# Kasli-SOC_IDC_EXT_Connectors.net
KiCad netlist of a schematic drawn in Altium Designer
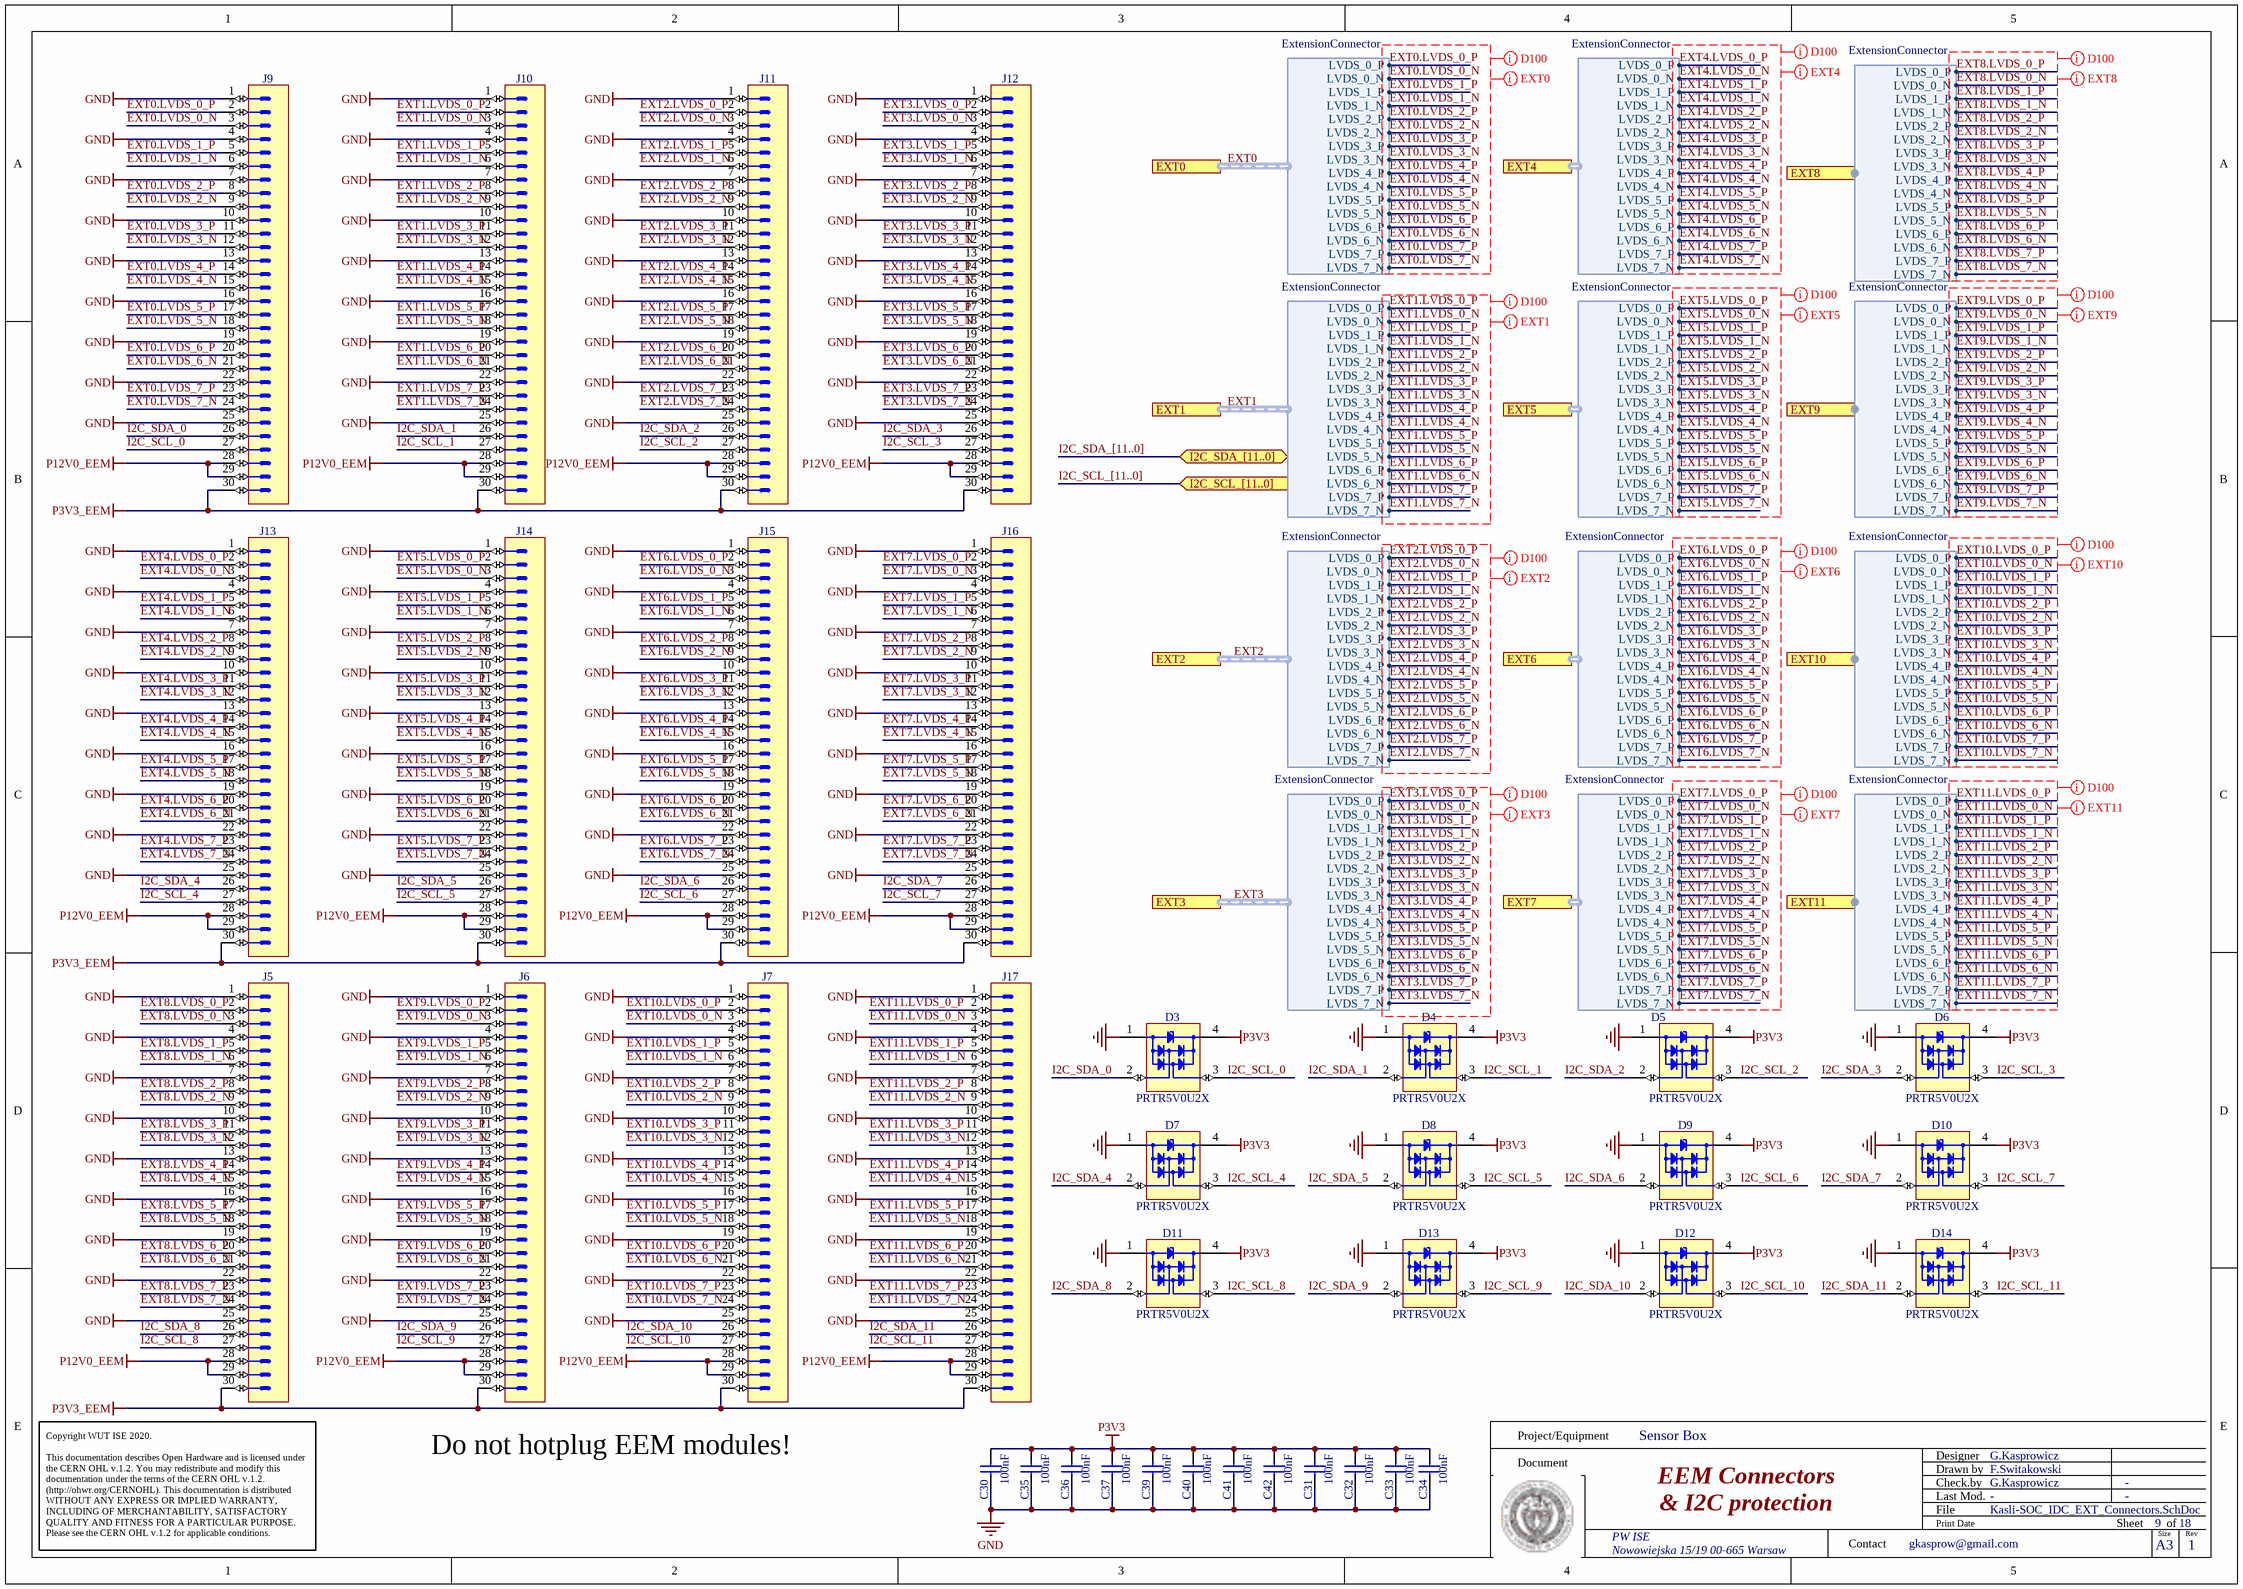
[diagram p0: Kasli-SOC_IDC_EXT_Connectors.SchDoc]

(export (version "E")
  (design (tool "Eeschema 10.0.6"))
  (components
    (comp (ref "C30")
      (value "100nF")
      (footprint "CAPC0603X33N")
      (description "Non-polarised capacitor")
      (fields
        (field (name "PART NUMBER") "CC0201_100NF_6.3V_10%_X5R")
        (field (name "VOLTAGE") "6.3V")
        (field (name "AUTHOR") "CERN DEM JLC")
      )
      (libsource (lib "Capacitors") (part "Capacitor - non polarized"))
    )
    (comp (ref "C31")
      (value "100nF")
      (footprint "CAPC0603X33N")
      (description "Non-polarised capacitor")
      (fields
        (field (name "PART NUMBER") "CC0201_100NF_6.3V_10%_X5R")
        (field (name "VOLTAGE") "6.3V")
        (field (name "AUTHOR") "CERN DEM JLC")
      )
      (libsource (lib "Capacitors") (part "Capacitor - non polarized"))
    )
    (comp (ref "C32")
      (value "100nF")
      (footprint "CAPC0603X33N")
      (description "Non-polarised capacitor")
      (fields
        (field (name "PART NUMBER") "CC0201_100NF_6.3V_10%_X5R")
        (field (name "VOLTAGE") "6.3V")
        (field (name "AUTHOR") "CERN DEM JLC")
      )
      (libsource (lib "Capacitors") (part "Capacitor - non polarized"))
    )
    (comp (ref "C33")
      (value "100nF")
      (footprint "CAPC0603X33N")
      (description "Non-polarised capacitor")
      (fields
        (field (name "PART NUMBER") "CC0201_100NF_6.3V_10%_X5R")
        (field (name "VOLTAGE") "6.3V")
        (field (name "AUTHOR") "CERN DEM JLC")
      )
      (libsource (lib "Capacitors") (part "Capacitor - non polarized"))
    )
    (comp (ref "C34")
      (value "100nF")
      (footprint "CAPC0603X33N")
      (description "Non-polarised capacitor")
      (fields
        (field (name "PART NUMBER") "CC0201_100NF_6.3V_10%_X5R")
        (field (name "VOLTAGE") "6.3V")
        (field (name "AUTHOR") "CERN DEM JLC")
      )
      (libsource (lib "Capacitors") (part "Capacitor - non polarized"))
    )
    (comp (ref "C35")
      (value "100nF")
      (footprint "CAPC0603X33N")
      (description "Non-polarised capacitor")
      (fields
        (field (name "PART NUMBER") "CC0201_100NF_6.3V_10%_X5R")
        (field (name "VOLTAGE") "6.3V")
        (field (name "AUTHOR") "CERN DEM JLC")
      )
      (libsource (lib "Capacitors") (part "Capacitor - non polarized"))
    )
    (comp (ref "C36")
      (value "100nF")
      (footprint "CAPC0603X33N")
      (description "Non-polarised capacitor")
      (fields
        (field (name "PART NUMBER") "CC0201_100NF_6.3V_10%_X5R")
        (field (name "VOLTAGE") "6.3V")
        (field (name "AUTHOR") "CERN DEM JLC")
      )
      (libsource (lib "Capacitors") (part "Capacitor - non polarized"))
    )
    (comp (ref "C37")
      (value "100nF")
      (footprint "CAPC0603X33N")
      (description "Non-polarised capacitor")
      (fields
        (field (name "PART NUMBER") "CC0201_100NF_6.3V_10%_X5R")
        (field (name "VOLTAGE") "6.3V")
        (field (name "AUTHOR") "CERN DEM JLC")
      )
      (libsource (lib "Capacitors") (part "Capacitor - non polarized"))
    )
    (comp (ref "C39")
      (value "100nF")
      (footprint "CAPC0603X33N")
      (description "Non-polarised capacitor")
      (fields
        (field (name "PART NUMBER") "CC0201_100NF_6.3V_10%_X5R")
        (field (name "VOLTAGE") "6.3V")
        (field (name "AUTHOR") "CERN DEM JLC")
      )
      (libsource (lib "Capacitors") (part "Capacitor - non polarized"))
    )
    (comp (ref "C40")
      (value "100nF")
      (footprint "CAPC0603X33N")
      (description "Non-polarised capacitor")
      (fields
        (field (name "PART NUMBER") "CC0201_100NF_6.3V_10%_X5R")
        (field (name "VOLTAGE") "6.3V")
        (field (name "AUTHOR") "CERN DEM JLC")
      )
      (libsource (lib "Capacitors") (part "Capacitor - non polarized"))
    )
    (comp (ref "C41")
      (value "100nF")
      (footprint "CAPC0603X33N")
      (description "Non-polarised capacitor")
      (fields
        (field (name "PART NUMBER") "CC0201_100NF_6.3V_10%_X5R")
        (field (name "VOLTAGE") "6.3V")
        (field (name "AUTHOR") "CERN DEM JLC")
      )
      (libsource (lib "Capacitors") (part "Capacitor - non polarized"))
    )
    (comp (ref "C42")
      (value "100nF")
      (footprint "CAPC0603X33N")
      (description "Non-polarised capacitor")
      (fields
        (field (name "PART NUMBER") "CC0201_100NF_6.3V_10%_X5R")
        (field (name "VOLTAGE") "6.3V")
        (field (name "AUTHOR") "CERN DEM JLC")
      )
      (libsource (lib "Capacitors") (part "Capacitor - non polarized"))
    )
    (comp (ref "D3")
      (value "PRTR5V0U2X")
      (footprint "SOT190P230X110-4N")
      (description "Ultra Low Capacitance Double Rail-to-Rail ESD Protection Diode")
      (fields
        (field (name "VOLTAGE") "5.5V")
        (field (name "MANUFACTURER") "NXP SEMICONDUCTORS")
        (field (name "AUTHOR") "CERN DEM JLC")
      )
      (libsource (lib "ICs And Semiconductors") (part "PRTR5V0U2X"))
    )
    (comp (ref "D4")
      (value "PRTR5V0U2X")
      (footprint "SOT190P230X110-4N")
      (description "Ultra Low Capacitance Double Rail-to-Rail ESD Protection Diode")
      (fields
        (field (name "VOLTAGE") "5.5V")
        (field (name "MANUFACTURER") "NXP SEMICONDUCTORS")
        (field (name "AUTHOR") "CERN DEM JLC")
      )
      (libsource (lib "ICs And Semiconductors") (part "PRTR5V0U2X"))
    )
    (comp (ref "D5")
      (value "PRTR5V0U2X")
      (footprint "SOT190P230X110-4N")
      (description "Ultra Low Capacitance Double Rail-to-Rail ESD Protection Diode")
      (fields
        (field (name "VOLTAGE") "5.5V")
        (field (name "MANUFACTURER") "NXP SEMICONDUCTORS")
        (field (name "AUTHOR") "CERN DEM JLC")
      )
      (libsource (lib "ICs And Semiconductors") (part "PRTR5V0U2X"))
    )
    (comp (ref "D6")
      (value "PRTR5V0U2X")
      (footprint "SOT190P230X110-4N")
      (description "Ultra Low Capacitance Double Rail-to-Rail ESD Protection Diode")
      (fields
        (field (name "VOLTAGE") "5.5V")
        (field (name "MANUFACTURER") "NXP SEMICONDUCTORS")
        (field (name "AUTHOR") "CERN DEM JLC")
      )
      (libsource (lib "ICs And Semiconductors") (part "PRTR5V0U2X"))
    )
    (comp (ref "D7")
      (value "PRTR5V0U2X")
      (footprint "SOT190P230X110-4N")
      (description "Ultra Low Capacitance Double Rail-to-Rail ESD Protection Diode")
      (fields
        (field (name "VOLTAGE") "5.5V")
        (field (name "MANUFACTURER") "NXP SEMICONDUCTORS")
        (field (name "AUTHOR") "CERN DEM JLC")
      )
      (libsource (lib "ICs And Semiconductors") (part "PRTR5V0U2X"))
    )
    (comp (ref "D8")
      (value "PRTR5V0U2X")
      (footprint "SOT190P230X110-4N")
      (description "Ultra Low Capacitance Double Rail-to-Rail ESD Protection Diode")
      (fields
        (field (name "VOLTAGE") "5.5V")
        (field (name "MANUFACTURER") "NXP SEMICONDUCTORS")
        (field (name "AUTHOR") "CERN DEM JLC")
      )
      (libsource (lib "ICs And Semiconductors") (part "PRTR5V0U2X"))
    )
    (comp (ref "D9")
      (value "PRTR5V0U2X")
      (footprint "SOT190P230X110-4N")
      (description "Ultra Low Capacitance Double Rail-to-Rail ESD Protection Diode")
      (fields
        (field (name "VOLTAGE") "5.5V")
        (field (name "MANUFACTURER") "NXP SEMICONDUCTORS")
        (field (name "AUTHOR") "CERN DEM JLC")
      )
      (libsource (lib "ICs And Semiconductors") (part "PRTR5V0U2X"))
    )
    (comp (ref "D10")
      (value "PRTR5V0U2X")
      (footprint "SOT190P230X110-4N")
      (description "Ultra Low Capacitance Double Rail-to-Rail ESD Protection Diode")
      (fields
        (field (name "VOLTAGE") "5.5V")
        (field (name "MANUFACTURER") "NXP SEMICONDUCTORS")
        (field (name "AUTHOR") "CERN DEM JLC")
      )
      (libsource (lib "ICs And Semiconductors") (part "PRTR5V0U2X"))
    )
    (comp (ref "D11")
      (value "PRTR5V0U2X")
      (footprint "SOT190P230X110-4N")
      (description "Ultra Low Capacitance Double Rail-to-Rail ESD Protection Diode")
      (fields
        (field (name "VOLTAGE") "5.5V")
        (field (name "MANUFACTURER") "NXP SEMICONDUCTORS")
        (field (name "AUTHOR") "CERN DEM JLC")
      )
      (libsource (lib "ICs And Semiconductors") (part "PRTR5V0U2X"))
    )
    (comp (ref "D12")
      (value "PRTR5V0U2X")
      (footprint "SOT190P230X110-4N")
      (description "Ultra Low Capacitance Double Rail-to-Rail ESD Protection Diode")
      (fields
        (field (name "VOLTAGE") "5.5V")
        (field (name "MANUFACTURER") "NXP SEMICONDUCTORS")
        (field (name "AUTHOR") "CERN DEM JLC")
      )
      (libsource (lib "ICs And Semiconductors") (part "PRTR5V0U2X"))
    )
    (comp (ref "D13")
      (value "PRTR5V0U2X")
      (footprint "SOT190P230X110-4N")
      (description "Ultra Low Capacitance Double Rail-to-Rail ESD Protection Diode")
      (fields
        (field (name "VOLTAGE") "5.5V")
        (field (name "MANUFACTURER") "NXP SEMICONDUCTORS")
        (field (name "AUTHOR") "CERN DEM JLC")
      )
      (libsource (lib "ICs And Semiconductors") (part "PRTR5V0U2X"))
    )
    (comp (ref "D14")
      (value "PRTR5V0U2X")
      (footprint "SOT190P230X110-4N")
      (description "Ultra Low Capacitance Double Rail-to-Rail ESD Protection Diode")
      (fields
        (field (name "VOLTAGE") "5.5V")
        (field (name "MANUFACTURER") "NXP SEMICONDUCTORS")
        (field (name "AUTHOR") "CERN DEM JLC")
      )
      (libsource (lib "ICs And Semiconductors") (part "PRTR5V0U2X"))
    )
    (comp (ref "J5")
      (value "~")
      (footprint "3M_N2530-6002RB")
      (description "Connector 30 Male")
      (fields
        (field (name "PART NUMBER") "3M_N2530-6002RB")
        (field (name "MANUFACTURER") "3M")
        (field (name "AUTHOR") "CERN DEM JLC")
      )
      (libsource (lib "Connectors") (part "Connector 30 Male"))
    )
    (comp (ref "J6")
      (value "~")
      (footprint "3M_N2530-6002RB")
      (description "Connector 30 Male")
      (fields
        (field (name "PART NUMBER") "3M_N2530-6002RB")
        (field (name "MANUFACTURER") "3M")
        (field (name "AUTHOR") "CERN DEM JLC")
      )
      (libsource (lib "Connectors") (part "Connector 30 Male"))
    )
    (comp (ref "J7")
      (value "~")
      (footprint "3M_N2530-6002RB")
      (description "Connector 30 Male")
      (fields
        (field (name "PART NUMBER") "3M_N2530-6002RB")
        (field (name "MANUFACTURER") "3M")
        (field (name "AUTHOR") "CERN DEM JLC")
      )
      (libsource (lib "Connectors") (part "Connector 30 Male"))
    )
    (comp (ref "J9")
      (value "~")
      (footprint "3M_N2530-6002RB")
      (description "Connector 30 Male")
      (fields
        (field (name "PART NUMBER") "3M_N2530-6002RB")
        (field (name "MANUFACTURER") "3M")
        (field (name "AUTHOR") "CERN DEM JLC")
      )
      (libsource (lib "Connectors") (part "Connector 30 Male"))
    )
    (comp (ref "J10")
      (value "~")
      (footprint "3M_N2530-6002RB")
      (description "Connector 30 Male")
      (fields
        (field (name "PART NUMBER") "3M_N2530-6002RB")
        (field (name "MANUFACTURER") "3M")
        (field (name "AUTHOR") "CERN DEM JLC")
      )
      (libsource (lib "Connectors") (part "Connector 30 Male"))
    )
    (comp (ref "J11")
      (value "~")
      (footprint "3M_N2530-6002RB")
      (description "Connector 30 Male")
      (fields
        (field (name "PART NUMBER") "3M_N2530-6002RB")
        (field (name "MANUFACTURER") "3M")
        (field (name "AUTHOR") "CERN DEM JLC")
      )
      (libsource (lib "Connectors") (part "Connector 30 Male"))
    )
    (comp (ref "J12")
      (value "~")
      (footprint "3M_N2530-6002RB")
      (description "Connector 30 Male")
      (fields
        (field (name "PART NUMBER") "3M_N2530-6002RB")
        (field (name "MANUFACTURER") "3M")
        (field (name "AUTHOR") "CERN DEM JLC")
      )
      (libsource (lib "Connectors") (part "Connector 30 Male"))
    )
    (comp (ref "J13")
      (value "~")
      (footprint "3M_N2530-6002RB")
      (description "Connector 30 Male")
      (fields
        (field (name "PART NUMBER") "3M_N2530-6002RB")
        (field (name "MANUFACTURER") "3M")
        (field (name "AUTHOR") "CERN DEM JLC")
      )
      (libsource (lib "Connectors") (part "Connector 30 Male"))
    )
    (comp (ref "J14")
      (value "~")
      (footprint "3M_N2530-6002RB")
      (description "Connector 30 Male")
      (fields
        (field (name "PART NUMBER") "3M_N2530-6002RB")
        (field (name "MANUFACTURER") "3M")
        (field (name "AUTHOR") "CERN DEM JLC")
      )
      (libsource (lib "Connectors") (part "Connector 30 Male"))
    )
    (comp (ref "J15")
      (value "~")
      (footprint "3M_N2530-6002RB")
      (description "Connector 30 Male")
      (fields
        (field (name "PART NUMBER") "3M_N2530-6002RB")
        (field (name "MANUFACTURER") "3M")
        (field (name "AUTHOR") "CERN DEM JLC")
      )
      (libsource (lib "Connectors") (part "Connector 30 Male"))
    )
    (comp (ref "J16")
      (value "~")
      (footprint "3M_N2530-6002RB")
      (description "Connector 30 Male")
      (fields
        (field (name "PART NUMBER") "3M_N2530-6002RB")
        (field (name "MANUFACTURER") "3M")
        (field (name "AUTHOR") "CERN DEM JLC")
      )
      (libsource (lib "Connectors") (part "Connector 30 Male"))
    )
    (comp (ref "J17")
      (value "~")
      (footprint "3M_N2530-6002RB")
      (description "Connector 30 Male")
      (fields
        (field (name "PART NUMBER") "3M_N2530-6002RB")
        (field (name "MANUFACTURER") "3M")
        (field (name "AUTHOR") "CERN DEM JLC")
      )
      (libsource (lib "Connectors") (part "Connector 30 Male"))
    )
  )
  (nets
    (net (code "6") (name "/EXT0.LVDS_0_N") (class "Default")
      (node (ref "J9") (pin "3") (pinfunction "3_3") (pintype "bidirectional"))
    )
    (net (code "7") (name "/EXT0.LVDS_0_P") (class "Default")
      (node (ref "J9") (pin "2") (pinfunction "2_2") (pintype "bidirectional"))
    )
    (net (code "8") (name "/EXT0.LVDS_1_N") (class "Default")
      (node (ref "J9") (pin "6") (pinfunction "6_6") (pintype "bidirectional"))
    )
    (net (code "9") (name "/EXT0.LVDS_1_P") (class "Default")
      (node (ref "J9") (pin "5") (pinfunction "5_5") (pintype "bidirectional"))
    )
    (net (code "10") (name "/EXT0.LVDS_2_N") (class "Default")
      (node (ref "J9") (pin "9") (pinfunction "9_9") (pintype "bidirectional"))
    )
    (net (code "11") (name "/EXT0.LVDS_2_P") (class "Default")
      (node (ref "J9") (pin "8") (pinfunction "8_8") (pintype "bidirectional"))
    )
    (net (code "12") (name "/EXT0.LVDS_3_N") (class "Default")
      (node (ref "J9") (pin "12") (pinfunction "12_12") (pintype "bidirectional"))
    )
    (net (code "13") (name "/EXT0.LVDS_3_P") (class "Default")
      (node (ref "J9") (pin "11") (pinfunction "11_11") (pintype "bidirectional"))
    )
    (net (code "14") (name "/EXT0.LVDS_4_N") (class "Default")
      (node (ref "J9") (pin "15") (pinfunction "15_15") (pintype "bidirectional"))
    )
    (net (code "15") (name "/EXT0.LVDS_4_P") (class "Default")
      (node (ref "J9") (pin "14") (pinfunction "14_14") (pintype "bidirectional"))
    )
    (net (code "16") (name "/EXT0.LVDS_5_N") (class "Default")
      (node (ref "J9") (pin "18") (pinfunction "18_18") (pintype "bidirectional"))
    )
    (net (code "17") (name "/EXT0.LVDS_5_P") (class "Default")
      (node (ref "J9") (pin "17") (pinfunction "17_17") (pintype "bidirectional"))
    )
    (net (code "18") (name "/EXT0.LVDS_6_N") (class "Default")
      (node (ref "J9") (pin "21") (pinfunction "21_21") (pintype "bidirectional"))
    )
    (net (code "19") (name "/EXT0.LVDS_6_P") (class "Default")
      (node (ref "J9") (pin "20") (pinfunction "20_20") (pintype "bidirectional"))
    )
    (net (code "20") (name "/EXT0.LVDS_7_N") (class "Default")
      (node (ref "J9") (pin "24") (pinfunction "24_24") (pintype "bidirectional"))
    )
    (net (code "21") (name "/EXT0.LVDS_7_P") (class "Default")
      (node (ref "J9") (pin "23") (pinfunction "23_23") (pintype "bidirectional"))
    )
    (net (code "23") (name "/EXT1.LVDS_0_N") (class "Default")
      (node (ref "J10") (pin "3") (pinfunction "3_3") (pintype "bidirectional"))
    )
    (net (code "24") (name "/EXT1.LVDS_0_P") (class "Default")
      (node (ref "J10") (pin "2") (pinfunction "2_2") (pintype "bidirectional"))
    )
    (net (code "25") (name "/EXT1.LVDS_1_N") (class "Default")
      (node (ref "J10") (pin "6") (pinfunction "6_6") (pintype "bidirectional"))
    )
    (net (code "26") (name "/EXT1.LVDS_1_P") (class "Default")
      (node (ref "J10") (pin "5") (pinfunction "5_5") (pintype "bidirectional"))
    )
    (net (code "27") (name "/EXT1.LVDS_2_N") (class "Default")
      (node (ref "J10") (pin "9") (pinfunction "9_9") (pintype "bidirectional"))
    )
    (net (code "28") (name "/EXT1.LVDS_2_P") (class "Default")
      (node (ref "J10") (pin "8") (pinfunction "8_8") (pintype "bidirectional"))
    )
    (net (code "29") (name "/EXT1.LVDS_3_N") (class "Default")
      (node (ref "J10") (pin "12") (pinfunction "12_12") (pintype "bidirectional"))
    )
    (net (code "30") (name "/EXT1.LVDS_3_P") (class "Default")
      (node (ref "J10") (pin "11") (pinfunction "11_11") (pintype "bidirectional"))
    )
    (net (code "31") (name "/EXT1.LVDS_4_N") (class "Default")
      (node (ref "J10") (pin "15") (pinfunction "15_15") (pintype "bidirectional"))
    )
    (net (code "32") (name "/EXT1.LVDS_4_P") (class "Default")
      (node (ref "J10") (pin "14") (pinfunction "14_14") (pintype "bidirectional"))
    )
    (net (code "33") (name "/EXT1.LVDS_5_N") (class "Default")
      (node (ref "J10") (pin "18") (pinfunction "18_18") (pintype "bidirectional"))
    )
    (net (code "34") (name "/EXT1.LVDS_5_P") (class "Default")
      (node (ref "J10") (pin "17") (pinfunction "17_17") (pintype "bidirectional"))
    )
    (net (code "35") (name "/EXT1.LVDS_6_N") (class "Default")
      (node (ref "J10") (pin "21") (pinfunction "21_21") (pintype "bidirectional"))
    )
    (net (code "36") (name "/EXT1.LVDS_6_P") (class "Default")
      (node (ref "J10") (pin "20") (pinfunction "20_20") (pintype "bidirectional"))
    )
    (net (code "37") (name "/EXT1.LVDS_7_N") (class "Default")
      (node (ref "J10") (pin "24") (pinfunction "24_24") (pintype "bidirectional"))
    )
    (net (code "38") (name "/EXT1.LVDS_7_P") (class "Default")
      (node (ref "J10") (pin "23") (pinfunction "23_23") (pintype "bidirectional"))
    )
    (net (code "40") (name "/EXT2.LVDS_0_N") (class "Default")
      (node (ref "J11") (pin "3") (pinfunction "3_3") (pintype "bidirectional"))
    )
    (net (code "41") (name "/EXT2.LVDS_0_P") (class "Default")
      (node (ref "J11") (pin "2") (pinfunction "2_2") (pintype "bidirectional"))
    )
    (net (code "42") (name "/EXT2.LVDS_1_N") (class "Default")
      (node (ref "J11") (pin "6") (pinfunction "6_6") (pintype "bidirectional"))
    )
    (net (code "43") (name "/EXT2.LVDS_1_P") (class "Default")
      (node (ref "J11") (pin "5") (pinfunction "5_5") (pintype "bidirectional"))
    )
    (net (code "44") (name "/EXT2.LVDS_2_N") (class "Default")
      (node (ref "J11") (pin "9") (pinfunction "9_9") (pintype "bidirectional"))
    )
    (net (code "45") (name "/EXT2.LVDS_2_P") (class "Default")
      (node (ref "J11") (pin "8") (pinfunction "8_8") (pintype "bidirectional"))
    )
    (net (code "46") (name "/EXT2.LVDS_3_N") (class "Default")
      (node (ref "J11") (pin "12") (pinfunction "12_12") (pintype "bidirectional"))
    )
    (net (code "47") (name "/EXT2.LVDS_3_P") (class "Default")
      (node (ref "J11") (pin "11") (pinfunction "11_11") (pintype "bidirectional"))
    )
    (net (code "48") (name "/EXT2.LVDS_4_N") (class "Default")
      (node (ref "J11") (pin "15") (pinfunction "15_15") (pintype "bidirectional"))
    )
    (net (code "49") (name "/EXT2.LVDS_4_P") (class "Default")
      (node (ref "J11") (pin "14") (pinfunction "14_14") (pintype "bidirectional"))
    )
    (net (code "50") (name "/EXT2.LVDS_5_N") (class "Default")
      (node (ref "J11") (pin "18") (pinfunction "18_18") (pintype "bidirectional"))
    )
    (net (code "51") (name "/EXT2.LVDS_5_P") (class "Default")
      (node (ref "J11") (pin "17") (pinfunction "17_17") (pintype "bidirectional"))
    )
    (net (code "52") (name "/EXT2.LVDS_6_N") (class "Default")
      (node (ref "J11") (pin "21") (pinfunction "21_21") (pintype "bidirectional"))
    )
    (net (code "53") (name "/EXT2.LVDS_6_P") (class "Default")
      (node (ref "J11") (pin "20") (pinfunction "20_20") (pintype "bidirectional"))
    )
    (net (code "54") (name "/EXT2.LVDS_7_N") (class "Default")
      (node (ref "J11") (pin "24") (pinfunction "24_24") (pintype "bidirectional"))
    )
    (net (code "55") (name "/EXT2.LVDS_7_P") (class "Default")
      (node (ref "J11") (pin "23") (pinfunction "23_23") (pintype "bidirectional"))
    )
    (net (code "57") (name "/EXT3.LVDS_0_N") (class "Default")
      (node (ref "J12") (pin "3") (pinfunction "3_3") (pintype "bidirectional"))
    )
    (net (code "58") (name "/EXT3.LVDS_0_P") (class "Default")
      (node (ref "J12") (pin "2") (pinfunction "2_2") (pintype "bidirectional"))
    )
    (net (code "59") (name "/EXT3.LVDS_1_N") (class "Default")
      (node (ref "J12") (pin "6") (pinfunction "6_6") (pintype "bidirectional"))
    )
    (net (code "60") (name "/EXT3.LVDS_1_P") (class "Default")
      (node (ref "J12") (pin "5") (pinfunction "5_5") (pintype "bidirectional"))
    )
    (net (code "61") (name "/EXT3.LVDS_2_N") (class "Default")
      (node (ref "J12") (pin "9") (pinfunction "9_9") (pintype "bidirectional"))
    )
    (net (code "62") (name "/EXT3.LVDS_2_P") (class "Default")
      (node (ref "J12") (pin "8") (pinfunction "8_8") (pintype "bidirectional"))
    )
    (net (code "63") (name "/EXT3.LVDS_3_N") (class "Default")
      (node (ref "J12") (pin "12") (pinfunction "12_12") (pintype "bidirectional"))
    )
    (net (code "64") (name "/EXT3.LVDS_3_P") (class "Default")
      (node (ref "J12") (pin "11") (pinfunction "11_11") (pintype "bidirectional"))
    )
    (net (code "65") (name "/EXT3.LVDS_4_N") (class "Default")
      (node (ref "J12") (pin "15") (pinfunction "15_15") (pintype "bidirectional"))
    )
    (net (code "66") (name "/EXT3.LVDS_4_P") (class "Default")
      (node (ref "J12") (pin "14") (pinfunction "14_14") (pintype "bidirectional"))
    )
    (net (code "67") (name "/EXT3.LVDS_5_N") (class "Default")
      (node (ref "J12") (pin "18") (pinfunction "18_18") (pintype "bidirectional"))
    )
    (net (code "68") (name "/EXT3.LVDS_5_P") (class "Default")
      (node (ref "J12") (pin "17") (pinfunction "17_17") (pintype "bidirectional"))
    )
    (net (code "69") (name "/EXT3.LVDS_6_N") (class "Default")
      (node (ref "J12") (pin "21") (pinfunction "21_21") (pintype "bidirectional"))
    )
    (net (code "70") (name "/EXT3.LVDS_6_P") (class "Default")
      (node (ref "J12") (pin "20") (pinfunction "20_20") (pintype "bidirectional"))
    )
    (net (code "71") (name "/EXT3.LVDS_7_N") (class "Default")
      (node (ref "J12") (pin "24") (pinfunction "24_24") (pintype "bidirectional"))
    )
    (net (code "72") (name "/EXT3.LVDS_7_P") (class "Default")
      (node (ref "J12") (pin "23") (pinfunction "23_23") (pintype "bidirectional"))
    )
    (net (code "74") (name "/EXT4.LVDS_0_N") (class "Default")
      (node (ref "J13") (pin "3") (pinfunction "3_3") (pintype "bidirectional"))
    )
    (net (code "75") (name "/EXT4.LVDS_0_P") (class "Default")
      (node (ref "J13") (pin "2") (pinfunction "2_2") (pintype "bidirectional"))
    )
    (net (code "76") (name "/EXT4.LVDS_1_N") (class "Default")
      (node (ref "J13") (pin "6") (pinfunction "6_6") (pintype "bidirectional"))
    )
    (net (code "77") (name "/EXT4.LVDS_1_P") (class "Default")
      (node (ref "J13") (pin "5") (pinfunction "5_5") (pintype "bidirectional"))
    )
    (net (code "78") (name "/EXT4.LVDS_2_N") (class "Default")
      (node (ref "J13") (pin "9") (pinfunction "9_9") (pintype "bidirectional"))
    )
    (net (code "79") (name "/EXT4.LVDS_2_P") (class "Default")
      (node (ref "J13") (pin "8") (pinfunction "8_8") (pintype "bidirectional"))
    )
    (net (code "80") (name "/EXT4.LVDS_3_N") (class "Default")
      (node (ref "J13") (pin "12") (pinfunction "12_12") (pintype "bidirectional"))
    )
    (net (code "81") (name "/EXT4.LVDS_3_P") (class "Default")
      (node (ref "J13") (pin "11") (pinfunction "11_11") (pintype "bidirectional"))
    )
    (net (code "82") (name "/EXT4.LVDS_4_N") (class "Default")
      (node (ref "J13") (pin "15") (pinfunction "15_15") (pintype "bidirectional"))
    )
    (net (code "83") (name "/EXT4.LVDS_4_P") (class "Default")
      (node (ref "J13") (pin "14") (pinfunction "14_14") (pintype "bidirectional"))
    )
    (net (code "84") (name "/EXT4.LVDS_5_N") (class "Default")
      (node (ref "J13") (pin "18") (pinfunction "18_18") (pintype "bidirectional"))
    )
    (net (code "85") (name "/EXT4.LVDS_5_P") (class "Default")
      (node (ref "J13") (pin "17") (pinfunction "17_17") (pintype "bidirectional"))
    )
    (net (code "86") (name "/EXT4.LVDS_6_N") (class "Default")
      (node (ref "J13") (pin "21") (pinfunction "21_21") (pintype "bidirectional"))
    )
    (net (code "87") (name "/EXT4.LVDS_6_P") (class "Default")
      (node (ref "J13") (pin "20") (pinfunction "20_20") (pintype "bidirectional"))
    )
    (net (code "88") (name "/EXT4.LVDS_7_N") (class "Default")
      (node (ref "J13") (pin "24") (pinfunction "24_24") (pintype "bidirectional"))
    )
    (net (code "89") (name "/EXT4.LVDS_7_P") (class "Default")
      (node (ref "J13") (pin "23") (pinfunction "23_23") (pintype "bidirectional"))
    )
    (net (code "90") (name "/EXT5.LVDS_0_N") (class "Default")
      (node (ref "J14") (pin "3") (pinfunction "3_3") (pintype "bidirectional"))
    )
    (net (code "91") (name "/EXT5.LVDS_0_P") (class "Default")
      (node (ref "J14") (pin "2") (pinfunction "2_2") (pintype "bidirectional"))
    )
    (net (code "92") (name "/EXT5.LVDS_1_N") (class "Default")
      (node (ref "J14") (pin "6") (pinfunction "6_6") (pintype "bidirectional"))
    )
    (net (code "93") (name "/EXT5.LVDS_1_P") (class "Default")
      (node (ref "J14") (pin "5") (pinfunction "5_5") (pintype "bidirectional"))
    )
    (net (code "94") (name "/EXT5.LVDS_2_N") (class "Default")
      (node (ref "J14") (pin "9") (pinfunction "9_9") (pintype "bidirectional"))
    )
    (net (code "95") (name "/EXT5.LVDS_2_P") (class "Default")
      (node (ref "J14") (pin "8") (pinfunction "8_8") (pintype "bidirectional"))
    )
    (net (code "96") (name "/EXT5.LVDS_3_N") (class "Default")
      (node (ref "J14") (pin "12") (pinfunction "12_12") (pintype "bidirectional"))
    )
    (net (code "97") (name "/EXT5.LVDS_3_P") (class "Default")
      (node (ref "J14") (pin "11") (pinfunction "11_11") (pintype "bidirectional"))
    )
    (net (code "98") (name "/EXT5.LVDS_4_N") (class "Default")
      (node (ref "J14") (pin "15") (pinfunction "15_15") (pintype "bidirectional"))
    )
    (net (code "99") (name "/EXT5.LVDS_4_P") (class "Default")
      (node (ref "J14") (pin "14") (pinfunction "14_14") (pintype "bidirectional"))
    )
    (net (code "100") (name "/EXT5.LVDS_5_N") (class "Default")
      (node (ref "J14") (pin "18") (pinfunction "18_18") (pintype "bidirectional"))
    )
    (net (code "101") (name "/EXT5.LVDS_5_P") (class "Default")
      (node (ref "J14") (pin "17") (pinfunction "17_17") (pintype "bidirectional"))
    )
    (net (code "102") (name "/EXT5.LVDS_6_N") (class "Default")
      (node (ref "J14") (pin "21") (pinfunction "21_21") (pintype "bidirectional"))
    )
    (net (code "103") (name "/EXT5.LVDS_6_P") (class "Default")
      (node (ref "J14") (pin "20") (pinfunction "20_20") (pintype "bidirectional"))
    )
    (net (code "104") (name "/EXT5.LVDS_7_N") (class "Default")
      (node (ref "J14") (pin "24") (pinfunction "24_24") (pintype "bidirectional"))
    )
    (net (code "105") (name "/EXT5.LVDS_7_P") (class "Default")
      (node (ref "J14") (pin "23") (pinfunction "23_23") (pintype "bidirectional"))
    )
    (net (code "106") (name "/EXT6.LVDS_0_N") (class "Default")
      (node (ref "J15") (pin "3") (pinfunction "3_3") (pintype "bidirectional"))
    )
    (net (code "107") (name "/EXT6.LVDS_0_P") (class "Default")
      (node (ref "J15") (pin "2") (pinfunction "2_2") (pintype "bidirectional"))
    )
    (net (code "108") (name "/EXT6.LVDS_1_N") (class "Default")
      (node (ref "J15") (pin "6") (pinfunction "6_6") (pintype "bidirectional"))
    )
    (net (code "109") (name "/EXT6.LVDS_1_P") (class "Default")
      (node (ref "J15") (pin "5") (pinfunction "5_5") (pintype "bidirectional"))
    )
    (net (code "110") (name "/EXT6.LVDS_2_N") (class "Default")
      (node (ref "J15") (pin "9") (pinfunction "9_9") (pintype "bidirectional"))
    )
    (net (code "111") (name "/EXT6.LVDS_2_P") (class "Default")
      (node (ref "J15") (pin "8") (pinfunction "8_8") (pintype "bidirectional"))
    )
    (net (code "112") (name "/EXT6.LVDS_3_N") (class "Default")
      (node (ref "J15") (pin "12") (pinfunction "12_12") (pintype "bidirectional"))
    )
    (net (code "113") (name "/EXT6.LVDS_3_P") (class "Default")
      (node (ref "J15") (pin "11") (pinfunction "11_11") (pintype "bidirectional"))
    )
    (net (code "114") (name "/EXT6.LVDS_4_N") (class "Default")
      (node (ref "J15") (pin "15") (pinfunction "15_15") (pintype "bidirectional"))
    )
    (net (code "115") (name "/EXT6.LVDS_4_P") (class "Default")
      (node (ref "J15") (pin "14") (pinfunction "14_14") (pintype "bidirectional"))
    )
    (net (code "116") (name "/EXT6.LVDS_5_N") (class "Default")
      (node (ref "J15") (pin "18") (pinfunction "18_18") (pintype "bidirectional"))
    )
    (net (code "117") (name "/EXT6.LVDS_5_P") (class "Default")
      (node (ref "J15") (pin "17") (pinfunction "17_17") (pintype "bidirectional"))
    )
    (net (code "118") (name "/EXT6.LVDS_6_N") (class "Default")
      (node (ref "J15") (pin "21") (pinfunction "21_21") (pintype "bidirectional"))
    )
    (net (code "119") (name "/EXT6.LVDS_6_P") (class "Default")
      (node (ref "J15") (pin "20") (pinfunction "20_20") (pintype "bidirectional"))
    )
    (net (code "120") (name "/EXT6.LVDS_7_N") (class "Default")
      (node (ref "J15") (pin "24") (pinfunction "24_24") (pintype "bidirectional"))
    )
    (net (code "121") (name "/EXT6.LVDS_7_P") (class "Default")
      (node (ref "J15") (pin "23") (pinfunction "23_23") (pintype "bidirectional"))
    )
    (net (code "122") (name "/EXT7.LVDS_0_N") (class "Default")
      (node (ref "J16") (pin "3") (pinfunction "3_3") (pintype "bidirectional"))
    )
    (net (code "123") (name "/EXT7.LVDS_0_P") (class "Default")
      (node (ref "J16") (pin "2") (pinfunction "2_2") (pintype "bidirectional"))
    )
    (net (code "124") (name "/EXT7.LVDS_1_N") (class "Default")
      (node (ref "J16") (pin "6") (pinfunction "6_6") (pintype "bidirectional"))
    )
    (net (code "125") (name "/EXT7.LVDS_1_P") (class "Default")
      (node (ref "J16") (pin "5") (pinfunction "5_5") (pintype "bidirectional"))
    )
    (net (code "126") (name "/EXT7.LVDS_2_N") (class "Default")
      (node (ref "J16") (pin "9") (pinfunction "9_9") (pintype "bidirectional"))
    )
    (net (code "127") (name "/EXT7.LVDS_2_P") (class "Default")
      (node (ref "J16") (pin "8") (pinfunction "8_8") (pintype "bidirectional"))
    )
    (net (code "128") (name "/EXT7.LVDS_3_N") (class "Default")
      (node (ref "J16") (pin "12") (pinfunction "12_12") (pintype "bidirectional"))
    )
    (net (code "129") (name "/EXT7.LVDS_3_P") (class "Default")
      (node (ref "J16") (pin "11") (pinfunction "11_11") (pintype "bidirectional"))
    )
    (net (code "130") (name "/EXT7.LVDS_4_N") (class "Default")
      (node (ref "J16") (pin "15") (pinfunction "15_15") (pintype "bidirectional"))
    )
    (net (code "131") (name "/EXT7.LVDS_4_P") (class "Default")
      (node (ref "J16") (pin "14") (pinfunction "14_14") (pintype "bidirectional"))
    )
    (net (code "132") (name "/EXT7.LVDS_5_N") (class "Default")
      (node (ref "J16") (pin "18") (pinfunction "18_18") (pintype "bidirectional"))
    )
    (net (code "133") (name "/EXT7.LVDS_5_P") (class "Default")
      (node (ref "J16") (pin "17") (pinfunction "17_17") (pintype "bidirectional"))
    )
    (net (code "134") (name "/EXT7.LVDS_6_N") (class "Default")
      (node (ref "J16") (pin "21") (pinfunction "21_21") (pintype "bidirectional"))
    )
    (net (code "135") (name "/EXT7.LVDS_6_P") (class "Default")
      (node (ref "J16") (pin "20") (pinfunction "20_20") (pintype "bidirectional"))
    )
    (net (code "136") (name "/EXT7.LVDS_7_N") (class "Default")
      (node (ref "J16") (pin "24") (pinfunction "24_24") (pintype "bidirectional"))
    )
    (net (code "137") (name "/EXT7.LVDS_7_P") (class "Default")
      (node (ref "J16") (pin "23") (pinfunction "23_23") (pintype "bidirectional"))
    )
    (net (code "138") (name "/EXT8.LVDS_0_N") (class "Default")
      (node (ref "J5") (pin "3") (pinfunction "3_3") (pintype "bidirectional"))
    )
    (net (code "139") (name "/EXT8.LVDS_0_P") (class "Default")
      (node (ref "J5") (pin "2") (pinfunction "2_2") (pintype "bidirectional"))
    )
    (net (code "140") (name "/EXT8.LVDS_1_N") (class "Default")
      (node (ref "J5") (pin "6") (pinfunction "6_6") (pintype "bidirectional"))
    )
    (net (code "141") (name "/EXT8.LVDS_1_P") (class "Default")
      (node (ref "J5") (pin "5") (pinfunction "5_5") (pintype "bidirectional"))
    )
    (net (code "142") (name "/EXT8.LVDS_2_N") (class "Default")
      (node (ref "J5") (pin "9") (pinfunction "9_9") (pintype "bidirectional"))
    )
    (net (code "143") (name "/EXT8.LVDS_2_P") (class "Default")
      (node (ref "J5") (pin "8") (pinfunction "8_8") (pintype "bidirectional"))
    )
    (net (code "144") (name "/EXT8.LVDS_3_N") (class "Default")
      (node (ref "J5") (pin "12") (pinfunction "12_12") (pintype "bidirectional"))
    )
    (net (code "145") (name "/EXT8.LVDS_3_P") (class "Default")
      (node (ref "J5") (pin "11") (pinfunction "11_11") (pintype "bidirectional"))
    )
    (net (code "146") (name "/EXT8.LVDS_4_N") (class "Default")
      (node (ref "J5") (pin "15") (pinfunction "15_15") (pintype "bidirectional"))
    )
    (net (code "147") (name "/EXT8.LVDS_4_P") (class "Default")
      (node (ref "J5") (pin "14") (pinfunction "14_14") (pintype "bidirectional"))
    )
    (net (code "148") (name "/EXT8.LVDS_5_N") (class "Default")
      (node (ref "J5") (pin "18") (pinfunction "18_18") (pintype "bidirectional"))
    )
    (net (code "149") (name "/EXT8.LVDS_5_P") (class "Default")
      (node (ref "J5") (pin "17") (pinfunction "17_17") (pintype "bidirectional"))
    )
    (net (code "150") (name "/EXT8.LVDS_6_N") (class "Default")
      (node (ref "J5") (pin "21") (pinfunction "21_21") (pintype "bidirectional"))
    )
    (net (code "151") (name "/EXT8.LVDS_6_P") (class "Default")
      (node (ref "J5") (pin "20") (pinfunction "20_20") (pintype "bidirectional"))
    )
    (net (code "152") (name "/EXT8.LVDS_7_N") (class "Default")
      (node (ref "J5") (pin "24") (pinfunction "24_24") (pintype "bidirectional"))
    )
    (net (code "153") (name "/EXT8.LVDS_7_P") (class "Default")
      (node (ref "J5") (pin "23") (pinfunction "23_23") (pintype "bidirectional"))
    )
    (net (code "154") (name "/EXT9.LVDS_0_N") (class "Default")
      (node (ref "J6") (pin "3") (pinfunction "3_3") (pintype "bidirectional"))
    )
    (net (code "155") (name "/EXT9.LVDS_0_P") (class "Default")
      (node (ref "J6") (pin "2") (pinfunction "2_2") (pintype "bidirectional"))
    )
    (net (code "156") (name "/EXT9.LVDS_1_N") (class "Default")
      (node (ref "J6") (pin "6") (pinfunction "6_6") (pintype "bidirectional"))
    )
    (net (code "157") (name "/EXT9.LVDS_1_P") (class "Default")
      (node (ref "J6") (pin "5") (pinfunction "5_5") (pintype "bidirectional"))
    )
    (net (code "158") (name "/EXT9.LVDS_2_N") (class "Default")
      (node (ref "J6") (pin "9") (pinfunction "9_9") (pintype "bidirectional"))
    )
    (net (code "159") (name "/EXT9.LVDS_2_P") (class "Default")
      (node (ref "J6") (pin "8") (pinfunction "8_8") (pintype "bidirectional"))
    )
    (net (code "160") (name "/EXT9.LVDS_3_N") (class "Default")
      (node (ref "J6") (pin "12") (pinfunction "12_12") (pintype "bidirectional"))
    )
    (net (code "161") (name "/EXT9.LVDS_3_P") (class "Default")
      (node (ref "J6") (pin "11") (pinfunction "11_11") (pintype "bidirectional"))
    )
    (net (code "162") (name "/EXT9.LVDS_4_N") (class "Default")
      (node (ref "J6") (pin "15") (pinfunction "15_15") (pintype "bidirectional"))
    )
    (net (code "163") (name "/EXT9.LVDS_4_P") (class "Default")
      (node (ref "J6") (pin "14") (pinfunction "14_14") (pintype "bidirectional"))
    )
    (net (code "164") (name "/EXT9.LVDS_5_N") (class "Default")
      (node (ref "J6") (pin "18") (pinfunction "18_18") (pintype "bidirectional"))
    )
    (net (code "165") (name "/EXT9.LVDS_5_P") (class "Default")
      (node (ref "J6") (pin "17") (pinfunction "17_17") (pintype "bidirectional"))
    )
    (net (code "166") (name "/EXT9.LVDS_6_N") (class "Default")
      (node (ref "J6") (pin "21") (pinfunction "21_21") (pintype "bidirectional"))
    )
    (net (code "167") (name "/EXT9.LVDS_6_P") (class "Default")
      (node (ref "J6") (pin "20") (pinfunction "20_20") (pintype "bidirectional"))
    )
    (net (code "168") (name "/EXT9.LVDS_7_N") (class "Default")
      (node (ref "J6") (pin "24") (pinfunction "24_24") (pintype "bidirectional"))
    )
    (net (code "169") (name "/EXT9.LVDS_7_P") (class "Default")
      (node (ref "J6") (pin "23") (pinfunction "23_23") (pintype "bidirectional"))
    )
    (net (code "170") (name "/EXT10.LVDS_0_N") (class "Default")
      (node (ref "J7") (pin "3") (pinfunction "3_3") (pintype "bidirectional"))
    )
    (net (code "171") (name "/EXT10.LVDS_0_P") (class "Default")
      (node (ref "J7") (pin "2") (pinfunction "2_2") (pintype "bidirectional"))
    )
    (net (code "172") (name "/EXT10.LVDS_1_N") (class "Default")
      (node (ref "J7") (pin "6") (pinfunction "6_6") (pintype "bidirectional"))
    )
    (net (code "173") (name "/EXT10.LVDS_1_P") (class "Default")
      (node (ref "J7") (pin "5") (pinfunction "5_5") (pintype "bidirectional"))
    )
    (net (code "174") (name "/EXT10.LVDS_2_N") (class "Default")
      (node (ref "J7") (pin "9") (pinfunction "9_9") (pintype "bidirectional"))
    )
    (net (code "175") (name "/EXT10.LVDS_2_P") (class "Default")
      (node (ref "J7") (pin "8") (pinfunction "8_8") (pintype "bidirectional"))
    )
    (net (code "176") (name "/EXT10.LVDS_3_N") (class "Default")
      (node (ref "J7") (pin "12") (pinfunction "12_12") (pintype "bidirectional"))
    )
    (net (code "177") (name "/EXT10.LVDS_3_P") (class "Default")
      (node (ref "J7") (pin "11") (pinfunction "11_11") (pintype "bidirectional"))
    )
    (net (code "178") (name "/EXT10.LVDS_4_N") (class "Default")
      (node (ref "J7") (pin "15") (pinfunction "15_15") (pintype "bidirectional"))
    )
    (net (code "179") (name "/EXT10.LVDS_4_P") (class "Default")
      (node (ref "J7") (pin "14") (pinfunction "14_14") (pintype "bidirectional"))
    )
    (net (code "180") (name "/EXT10.LVDS_5_N") (class "Default")
      (node (ref "J7") (pin "18") (pinfunction "18_18") (pintype "bidirectional"))
    )
    (net (code "181") (name "/EXT10.LVDS_5_P") (class "Default")
      (node (ref "J7") (pin "17") (pinfunction "17_17") (pintype "bidirectional"))
    )
    (net (code "182") (name "/EXT10.LVDS_6_N") (class "Default")
      (node (ref "J7") (pin "21") (pinfunction "21_21") (pintype "bidirectional"))
    )
    (net (code "183") (name "/EXT10.LVDS_6_P") (class "Default")
      (node (ref "J7") (pin "20") (pinfunction "20_20") (pintype "bidirectional"))
    )
    (net (code "184") (name "/EXT10.LVDS_7_N") (class "Default")
      (node (ref "J7") (pin "24") (pinfunction "24_24") (pintype "bidirectional"))
    )
    (net (code "185") (name "/EXT10.LVDS_7_P") (class "Default")
      (node (ref "J7") (pin "23") (pinfunction "23_23") (pintype "bidirectional"))
    )
    (net (code "186") (name "/EXT11.LVDS_0_N") (class "Default")
      (node (ref "J17") (pin "3") (pinfunction "3_3") (pintype "bidirectional"))
    )
    (net (code "187") (name "/EXT11.LVDS_0_P") (class "Default")
      (node (ref "J17") (pin "2") (pinfunction "2_2") (pintype "bidirectional"))
    )
    (net (code "188") (name "/EXT11.LVDS_1_N") (class "Default")
      (node (ref "J17") (pin "6") (pinfunction "6_6") (pintype "bidirectional"))
    )
    (net (code "189") (name "/EXT11.LVDS_1_P") (class "Default")
      (node (ref "J17") (pin "5") (pinfunction "5_5") (pintype "bidirectional"))
    )
    (net (code "190") (name "/EXT11.LVDS_2_N") (class "Default")
      (node (ref "J17") (pin "9") (pinfunction "9_9") (pintype "bidirectional"))
    )
    (net (code "191") (name "/EXT11.LVDS_2_P") (class "Default")
      (node (ref "J17") (pin "8") (pinfunction "8_8") (pintype "bidirectional"))
    )
    (net (code "192") (name "/EXT11.LVDS_3_N") (class "Default")
      (node (ref "J17") (pin "12") (pinfunction "12_12") (pintype "bidirectional"))
    )
    (net (code "193") (name "/EXT11.LVDS_3_P") (class "Default")
      (node (ref "J17") (pin "11") (pinfunction "11_11") (pintype "bidirectional"))
    )
    (net (code "194") (name "/EXT11.LVDS_4_N") (class "Default")
      (node (ref "J17") (pin "15") (pinfunction "15_15") (pintype "bidirectional"))
    )
    (net (code "195") (name "/EXT11.LVDS_4_P") (class "Default")
      (node (ref "J17") (pin "14") (pinfunction "14_14") (pintype "bidirectional"))
    )
    (net (code "196") (name "/EXT11.LVDS_5_N") (class "Default")
      (node (ref "J17") (pin "18") (pinfunction "18_18") (pintype "bidirectional"))
    )
    (net (code "197") (name "/EXT11.LVDS_5_P") (class "Default")
      (node (ref "J17") (pin "17") (pinfunction "17_17") (pintype "bidirectional"))
    )
    (net (code "198") (name "/EXT11.LVDS_6_N") (class "Default")
      (node (ref "J17") (pin "21") (pinfunction "21_21") (pintype "bidirectional"))
    )
    (net (code "199") (name "/EXT11.LVDS_6_P") (class "Default")
      (node (ref "J17") (pin "20") (pinfunction "20_20") (pintype "bidirectional"))
    )
    (net (code "200") (name "/EXT11.LVDS_7_N") (class "Default")
      (node (ref "J17") (pin "24") (pinfunction "24_24") (pintype "bidirectional"))
    )
    (net (code "201") (name "/EXT11.LVDS_7_P") (class "Default")
      (node (ref "J17") (pin "23") (pinfunction "23_23") (pintype "bidirectional"))
    )
    (net (code "202") (name "/I2C_SCL_0") (class "Default")
      (node (ref "D3") (pin "3") (pinfunction "I/O2_3") (pintype "bidirectional"))
      (node (ref "J9") (pin "27") (pinfunction "27_27") (pintype "bidirectional"))
    )
    (net (code "203") (name "/I2C_SCL_1") (class "Default")
      (node (ref "D4") (pin "3") (pinfunction "I/O2_3") (pintype "bidirectional"))
      (node (ref "J10") (pin "27") (pinfunction "27_27") (pintype "bidirectional"))
    )
    (net (code "204") (name "/I2C_SCL_2") (class "Default")
      (node (ref "D5") (pin "3") (pinfunction "I/O2_3") (pintype "bidirectional"))
      (node (ref "J11") (pin "27") (pinfunction "27_27") (pintype "bidirectional"))
    )
    (net (code "205") (name "/I2C_SCL_3") (class "Default")
      (node (ref "D6") (pin "3") (pinfunction "I/O2_3") (pintype "bidirectional"))
      (node (ref "J12") (pin "27") (pinfunction "27_27") (pintype "bidirectional"))
    )
    (net (code "206") (name "/I2C_SCL_4") (class "Default")
      (node (ref "D7") (pin "3") (pinfunction "I/O2_3") (pintype "bidirectional"))
      (node (ref "J13") (pin "27") (pinfunction "27_27") (pintype "bidirectional"))
    )
    (net (code "207") (name "/I2C_SCL_5") (class "Default")
      (node (ref "D8") (pin "3") (pinfunction "I/O2_3") (pintype "bidirectional"))
      (node (ref "J14") (pin "27") (pinfunction "27_27") (pintype "bidirectional"))
    )
    (net (code "208") (name "/I2C_SCL_6") (class "Default")
      (node (ref "D9") (pin "3") (pinfunction "I/O2_3") (pintype "bidirectional"))
      (node (ref "J15") (pin "27") (pinfunction "27_27") (pintype "bidirectional"))
    )
    (net (code "209") (name "/I2C_SCL_7") (class "Default")
      (node (ref "D10") (pin "3") (pinfunction "I/O2_3") (pintype "bidirectional"))
      (node (ref "J16") (pin "27") (pinfunction "27_27") (pintype "bidirectional"))
    )
    (net (code "210") (name "/I2C_SCL_8") (class "Default")
      (node (ref "D11") (pin "3") (pinfunction "I/O2_3") (pintype "bidirectional"))
      (node (ref "J5") (pin "27") (pinfunction "27_27") (pintype "bidirectional"))
    )
    (net (code "211") (name "/I2C_SCL_9") (class "Default")
      (node (ref "D13") (pin "3") (pinfunction "I/O2_3") (pintype "bidirectional"))
      (node (ref "J6") (pin "27") (pinfunction "27_27") (pintype "bidirectional"))
    )
    (net (code "212") (name "/I2C_SCL_10") (class "Default")
      (node (ref "D12") (pin "3") (pinfunction "I/O2_3") (pintype "bidirectional"))
      (node (ref "J7") (pin "27") (pinfunction "27_27") (pintype "bidirectional"))
    )
    (net (code "213") (name "/I2C_SCL_11") (class "Default")
      (node (ref "D14") (pin "3") (pinfunction "I/O2_3") (pintype "bidirectional"))
      (node (ref "J17") (pin "27") (pinfunction "27_27") (pintype "bidirectional"))
    )
    (net (code "215") (name "/I2C_SDA_0") (class "Default")
      (node (ref "D3") (pin "2") (pinfunction "I/O1_2") (pintype "bidirectional"))
      (node (ref "J9") (pin "26") (pinfunction "26_26") (pintype "bidirectional"))
    )
    (net (code "216") (name "/I2C_SDA_1") (class "Default")
      (node (ref "D4") (pin "2") (pinfunction "I/O1_2") (pintype "bidirectional"))
      (node (ref "J10") (pin "26") (pinfunction "26_26") (pintype "bidirectional"))
    )
    (net (code "217") (name "/I2C_SDA_2") (class "Default")
      (node (ref "D5") (pin "2") (pinfunction "I/O1_2") (pintype "bidirectional"))
      (node (ref "J11") (pin "26") (pinfunction "26_26") (pintype "bidirectional"))
    )
    (net (code "218") (name "/I2C_SDA_3") (class "Default")
      (node (ref "D6") (pin "2") (pinfunction "I/O1_2") (pintype "bidirectional"))
      (node (ref "J12") (pin "26") (pinfunction "26_26") (pintype "bidirectional"))
    )
    (net (code "219") (name "/I2C_SDA_4") (class "Default")
      (node (ref "D7") (pin "2") (pinfunction "I/O1_2") (pintype "bidirectional"))
      (node (ref "J13") (pin "26") (pinfunction "26_26") (pintype "bidirectional"))
    )
    (net (code "220") (name "/I2C_SDA_5") (class "Default")
      (node (ref "D8") (pin "2") (pinfunction "I/O1_2") (pintype "bidirectional"))
      (node (ref "J14") (pin "26") (pinfunction "26_26") (pintype "bidirectional"))
    )
    (net (code "221") (name "/I2C_SDA_6") (class "Default")
      (node (ref "D9") (pin "2") (pinfunction "I/O1_2") (pintype "bidirectional"))
      (node (ref "J15") (pin "26") (pinfunction "26_26") (pintype "bidirectional"))
    )
    (net (code "222") (name "/I2C_SDA_7") (class "Default")
      (node (ref "D10") (pin "2") (pinfunction "I/O1_2") (pintype "bidirectional"))
      (node (ref "J16") (pin "26") (pinfunction "26_26") (pintype "bidirectional"))
    )
    (net (code "223") (name "/I2C_SDA_8") (class "Default")
      (node (ref "D11") (pin "2") (pinfunction "I/O1_2") (pintype "bidirectional"))
      (node (ref "J5") (pin "26") (pinfunction "26_26") (pintype "bidirectional"))
    )
    (net (code "224") (name "/I2C_SDA_9") (class "Default")
      (node (ref "D13") (pin "2") (pinfunction "I/O1_2") (pintype "bidirectional"))
      (node (ref "J6") (pin "26") (pinfunction "26_26") (pintype "bidirectional"))
    )
    (net (code "225") (name "/I2C_SDA_10") (class "Default")
      (node (ref "D12") (pin "2") (pinfunction "I/O1_2") (pintype "bidirectional"))
      (node (ref "J7") (pin "26") (pinfunction "26_26") (pintype "bidirectional"))
    )
    (net (code "226") (name "/I2C_SDA_11") (class "Default")
      (node (ref "D14") (pin "2") (pinfunction "I/O1_2") (pintype "bidirectional"))
      (node (ref "J17") (pin "26") (pinfunction "26_26") (pintype "bidirectional"))
    )
    (net (code "229") (name "GND") (class "Default")
      (node (ref "C30") (pin "1") (pinfunction "1_1") (pintype "passive"))
      (node (ref "C31") (pin "1") (pinfunction "1_1") (pintype "passive"))
      (node (ref "C32") (pin "1") (pinfunction "1_1") (pintype "passive"))
      (node (ref "C33") (pin "1") (pinfunction "1_1") (pintype "passive"))
      (node (ref "C34") (pin "1") (pinfunction "1_1") (pintype "passive"))
      (node (ref "C35") (pin "1") (pinfunction "1_1") (pintype "passive"))
      (node (ref "C36") (pin "1") (pinfunction "1_1") (pintype "passive"))
      (node (ref "C37") (pin "1") (pinfunction "1_1") (pintype "passive"))
      (node (ref "C39") (pin "1") (pinfunction "1_1") (pintype "passive"))
      (node (ref "C40") (pin "1") (pinfunction "1_1") (pintype "passive"))
      (node (ref "C41") (pin "1") (pinfunction "1_1") (pintype "passive"))
      (node (ref "C42") (pin "1") (pinfunction "1_1") (pintype "passive"))
      (node (ref "D10") (pin "1") (pinfunction "GND_1") (pintype "power_in"))
      (node (ref "D11") (pin "1") (pinfunction "GND_1") (pintype "power_in"))
      (node (ref "D12") (pin "1") (pinfunction "GND_1") (pintype "power_in"))
      (node (ref "D13") (pin "1") (pinfunction "GND_1") (pintype "power_in"))
      (node (ref "D14") (pin "1") (pinfunction "GND_1") (pintype "power_in"))
      (node (ref "D3") (pin "1") (pinfunction "GND_1") (pintype "power_in"))
      (node (ref "D4") (pin "1") (pinfunction "GND_1") (pintype "power_in"))
      (node (ref "D5") (pin "1") (pinfunction "GND_1") (pintype "power_in"))
      (node (ref "D6") (pin "1") (pinfunction "GND_1") (pintype "power_in"))
      (node (ref "D7") (pin "1") (pinfunction "GND_1") (pintype "power_in"))
      (node (ref "D8") (pin "1") (pinfunction "GND_1") (pintype "power_in"))
      (node (ref "D9") (pin "1") (pinfunction "GND_1") (pintype "power_in"))
      (node (ref "J10") (pin "1") (pinfunction "1_1") (pintype "bidirectional"))
      (node (ref "J10") (pin "10") (pinfunction "10_10") (pintype "bidirectional"))
      (node (ref "J10") (pin "13") (pinfunction "13_13") (pintype "bidirectional"))
      (node (ref "J10") (pin "16") (pinfunction "16_16") (pintype "bidirectional"))
      (node (ref "J10") (pin "19") (pinfunction "19_19") (pintype "bidirectional"))
      (node (ref "J10") (pin "22") (pinfunction "22_22") (pintype "bidirectional"))
      (node (ref "J10") (pin "25") (pinfunction "25_25") (pintype "bidirectional"))
      (node (ref "J10") (pin "4") (pinfunction "4_4") (pintype "bidirectional"))
      (node (ref "J10") (pin "7") (pinfunction "7_7") (pintype "bidirectional"))
      (node (ref "J11") (pin "1") (pinfunction "1_1") (pintype "bidirectional"))
      (node (ref "J11") (pin "10") (pinfunction "10_10") (pintype "bidirectional"))
      (node (ref "J11") (pin "13") (pinfunction "13_13") (pintype "bidirectional"))
      (node (ref "J11") (pin "16") (pinfunction "16_16") (pintype "bidirectional"))
      (node (ref "J11") (pin "19") (pinfunction "19_19") (pintype "bidirectional"))
      (node (ref "J11") (pin "22") (pinfunction "22_22") (pintype "bidirectional"))
      (node (ref "J11") (pin "25") (pinfunction "25_25") (pintype "bidirectional"))
      (node (ref "J11") (pin "4") (pinfunction "4_4") (pintype "bidirectional"))
      (node (ref "J11") (pin "7") (pinfunction "7_7") (pintype "bidirectional"))
      (node (ref "J12") (pin "1") (pinfunction "1_1") (pintype "bidirectional"))
      (node (ref "J12") (pin "10") (pinfunction "10_10") (pintype "bidirectional"))
      (node (ref "J12") (pin "13") (pinfunction "13_13") (pintype "bidirectional"))
      (node (ref "J12") (pin "16") (pinfunction "16_16") (pintype "bidirectional"))
      (node (ref "J12") (pin "19") (pinfunction "19_19") (pintype "bidirectional"))
      (node (ref "J12") (pin "22") (pinfunction "22_22") (pintype "bidirectional"))
      (node (ref "J12") (pin "25") (pinfunction "25_25") (pintype "bidirectional"))
      (node (ref "J12") (pin "4") (pinfunction "4_4") (pintype "bidirectional"))
      (node (ref "J12") (pin "7") (pinfunction "7_7") (pintype "bidirectional"))
      (node (ref "J13") (pin "1") (pinfunction "1_1") (pintype "bidirectional"))
      (node (ref "J13") (pin "10") (pinfunction "10_10") (pintype "bidirectional"))
      (node (ref "J13") (pin "13") (pinfunction "13_13") (pintype "bidirectional"))
      (node (ref "J13") (pin "16") (pinfunction "16_16") (pintype "bidirectional"))
      (node (ref "J13") (pin "19") (pinfunction "19_19") (pintype "bidirectional"))
      (node (ref "J13") (pin "22") (pinfunction "22_22") (pintype "bidirectional"))
      (node (ref "J13") (pin "25") (pinfunction "25_25") (pintype "bidirectional"))
      (node (ref "J13") (pin "4") (pinfunction "4_4") (pintype "bidirectional"))
      (node (ref "J13") (pin "7") (pinfunction "7_7") (pintype "bidirectional"))
      (node (ref "J14") (pin "1") (pinfunction "1_1") (pintype "bidirectional"))
      (node (ref "J14") (pin "10") (pinfunction "10_10") (pintype "bidirectional"))
      (node (ref "J14") (pin "13") (pinfunction "13_13") (pintype "bidirectional"))
      (node (ref "J14") (pin "16") (pinfunction "16_16") (pintype "bidirectional"))
      (node (ref "J14") (pin "19") (pinfunction "19_19") (pintype "bidirectional"))
      (node (ref "J14") (pin "22") (pinfunction "22_22") (pintype "bidirectional"))
      (node (ref "J14") (pin "25") (pinfunction "25_25") (pintype "bidirectional"))
      (node (ref "J14") (pin "4") (pinfunction "4_4") (pintype "bidirectional"))
      (node (ref "J14") (pin "7") (pinfunction "7_7") (pintype "bidirectional"))
      (node (ref "J15") (pin "1") (pinfunction "1_1") (pintype "bidirectional"))
      (node (ref "J15") (pin "10") (pinfunction "10_10") (pintype "bidirectional"))
      (node (ref "J15") (pin "13") (pinfunction "13_13") (pintype "bidirectional"))
      (node (ref "J15") (pin "16") (pinfunction "16_16") (pintype "bidirectional"))
      (node (ref "J15") (pin "19") (pinfunction "19_19") (pintype "bidirectional"))
      (node (ref "J15") (pin "22") (pinfunction "22_22") (pintype "bidirectional"))
      (node (ref "J15") (pin "25") (pinfunction "25_25") (pintype "bidirectional"))
      (node (ref "J15") (pin "4") (pinfunction "4_4") (pintype "bidirectional"))
      (node (ref "J15") (pin "7") (pinfunction "7_7") (pintype "bidirectional"))
      (node (ref "J16") (pin "1") (pinfunction "1_1") (pintype "bidirectional"))
      (node (ref "J16") (pin "10") (pinfunction "10_10") (pintype "bidirectional"))
      (node (ref "J16") (pin "13") (pinfunction "13_13") (pintype "bidirectional"))
      (node (ref "J16") (pin "16") (pinfunction "16_16") (pintype "bidirectional"))
      (node (ref "J16") (pin "19") (pinfunction "19_19") (pintype "bidirectional"))
      (node (ref "J16") (pin "22") (pinfunction "22_22") (pintype "bidirectional"))
      (node (ref "J16") (pin "25") (pinfunction "25_25") (pintype "bidirectional"))
      (node (ref "J16") (pin "4") (pinfunction "4_4") (pintype "bidirectional"))
      (node (ref "J16") (pin "7") (pinfunction "7_7") (pintype "bidirectional"))
      (node (ref "J17") (pin "1") (pinfunction "1_1") (pintype "bidirectional"))
      (node (ref "J17") (pin "10") (pinfunction "10_10") (pintype "bidirectional"))
      (node (ref "J17") (pin "13") (pinfunction "13_13") (pintype "bidirectional"))
      (node (ref "J17") (pin "16") (pinfunction "16_16") (pintype "bidirectional"))
      (node (ref "J17") (pin "19") (pinfunction "19_19") (pintype "bidirectional"))
      (node (ref "J17") (pin "22") (pinfunction "22_22") (pintype "bidirectional"))
      (node (ref "J17") (pin "25") (pinfunction "25_25") (pintype "bidirectional"))
      (node (ref "J17") (pin "4") (pinfunction "4_4") (pintype "bidirectional"))
      (node (ref "J17") (pin "7") (pinfunction "7_7") (pintype "bidirectional"))
      (node (ref "J5") (pin "1") (pinfunction "1_1") (pintype "bidirectional"))
      (node (ref "J5") (pin "10") (pinfunction "10_10") (pintype "bidirectional"))
      (node (ref "J5") (pin "13") (pinfunction "13_13") (pintype "bidirectional"))
      (node (ref "J5") (pin "16") (pinfunction "16_16") (pintype "bidirectional"))
      (node (ref "J5") (pin "19") (pinfunction "19_19") (pintype "bidirectional"))
      (node (ref "J5") (pin "22") (pinfunction "22_22") (pintype "bidirectional"))
      (node (ref "J5") (pin "25") (pinfunction "25_25") (pintype "bidirectional"))
      (node (ref "J5") (pin "4") (pinfunction "4_4") (pintype "bidirectional"))
      (node (ref "J5") (pin "7") (pinfunction "7_7") (pintype "bidirectional"))
      (node (ref "J6") (pin "1") (pinfunction "1_1") (pintype "bidirectional"))
      (node (ref "J6") (pin "10") (pinfunction "10_10") (pintype "bidirectional"))
      (node (ref "J6") (pin "13") (pinfunction "13_13") (pintype "bidirectional"))
      (node (ref "J6") (pin "16") (pinfunction "16_16") (pintype "bidirectional"))
      (node (ref "J6") (pin "19") (pinfunction "19_19") (pintype "bidirectional"))
      (node (ref "J6") (pin "22") (pinfunction "22_22") (pintype "bidirectional"))
      (node (ref "J6") (pin "25") (pinfunction "25_25") (pintype "bidirectional"))
      (node (ref "J6") (pin "4") (pinfunction "4_4") (pintype "bidirectional"))
      (node (ref "J6") (pin "7") (pinfunction "7_7") (pintype "bidirectional"))
      (node (ref "J7") (pin "1") (pinfunction "1_1") (pintype "bidirectional"))
      (node (ref "J7") (pin "10") (pinfunction "10_10") (pintype "bidirectional"))
      (node (ref "J7") (pin "13") (pinfunction "13_13") (pintype "bidirectional"))
      (node (ref "J7") (pin "16") (pinfunction "16_16") (pintype "bidirectional"))
      (node (ref "J7") (pin "19") (pinfunction "19_19") (pintype "bidirectional"))
      (node (ref "J7") (pin "22") (pinfunction "22_22") (pintype "bidirectional"))
      (node (ref "J7") (pin "25") (pinfunction "25_25") (pintype "bidirectional"))
      (node (ref "J7") (pin "4") (pinfunction "4_4") (pintype "bidirectional"))
      (node (ref "J7") (pin "7") (pinfunction "7_7") (pintype "bidirectional"))
      (node (ref "J9") (pin "1") (pinfunction "1_1") (pintype "bidirectional"))
      (node (ref "J9") (pin "10") (pinfunction "10_10") (pintype "bidirectional"))
      (node (ref "J9") (pin "13") (pinfunction "13_13") (pintype "bidirectional"))
      (node (ref "J9") (pin "16") (pinfunction "16_16") (pintype "bidirectional"))
      (node (ref "J9") (pin "19") (pinfunction "19_19") (pintype "bidirectional"))
      (node (ref "J9") (pin "22") (pinfunction "22_22") (pintype "bidirectional"))
      (node (ref "J9") (pin "25") (pinfunction "25_25") (pintype "bidirectional"))
      (node (ref "J9") (pin "4") (pinfunction "4_4") (pintype "bidirectional"))
      (node (ref "J9") (pin "7") (pinfunction "7_7") (pintype "bidirectional"))
    )
    (net (code "230") (name "P3V3") (class "Default")
      (node (ref "C30") (pin "2") (pinfunction "2_2") (pintype "passive"))
      (node (ref "C31") (pin "2") (pinfunction "2_2") (pintype "passive"))
      (node (ref "C32") (pin "2") (pinfunction "2_2") (pintype "passive"))
      (node (ref "C33") (pin "2") (pinfunction "2_2") (pintype "passive"))
      (node (ref "C34") (pin "2") (pinfunction "2_2") (pintype "passive"))
      (node (ref "C35") (pin "2") (pinfunction "2_2") (pintype "passive"))
      (node (ref "C36") (pin "2") (pinfunction "2_2") (pintype "passive"))
      (node (ref "C37") (pin "2") (pinfunction "2_2") (pintype "passive"))
      (node (ref "C39") (pin "2") (pinfunction "2_2") (pintype "passive"))
      (node (ref "C40") (pin "2") (pinfunction "2_2") (pintype "passive"))
      (node (ref "C41") (pin "2") (pinfunction "2_2") (pintype "passive"))
      (node (ref "C42") (pin "2") (pinfunction "2_2") (pintype "passive"))
      (node (ref "D10") (pin "4") (pinfunction "VCC_4") (pintype "power_in"))
      (node (ref "D11") (pin "4") (pinfunction "VCC_4") (pintype "power_in"))
      (node (ref "D12") (pin "4") (pinfunction "VCC_4") (pintype "power_in"))
      (node (ref "D13") (pin "4") (pinfunction "VCC_4") (pintype "power_in"))
      (node (ref "D14") (pin "4") (pinfunction "VCC_4") (pintype "power_in"))
      (node (ref "D3") (pin "4") (pinfunction "VCC_4") (pintype "power_in"))
      (node (ref "D4") (pin "4") (pinfunction "VCC_4") (pintype "power_in"))
      (node (ref "D5") (pin "4") (pinfunction "VCC_4") (pintype "power_in"))
      (node (ref "D6") (pin "4") (pinfunction "VCC_4") (pintype "power_in"))
      (node (ref "D7") (pin "4") (pinfunction "VCC_4") (pintype "power_in"))
      (node (ref "D8") (pin "4") (pinfunction "VCC_4") (pintype "power_in"))
      (node (ref "D9") (pin "4") (pinfunction "VCC_4") (pintype "power_in"))
    )
    (net (code "231") (name "P3V3_EEM") (class "Default")
      (node (ref "J10") (pin "30") (pinfunction "30_30") (pintype "bidirectional"))
      (node (ref "J11") (pin "30") (pinfunction "30_30") (pintype "bidirectional"))
      (node (ref "J12") (pin "30") (pinfunction "30_30") (pintype "bidirectional"))
      (node (ref "J13") (pin "30") (pinfunction "30_30") (pintype "bidirectional"))
      (node (ref "J14") (pin "30") (pinfunction "30_30") (pintype "bidirectional"))
      (node (ref "J15") (pin "30") (pinfunction "30_30") (pintype "bidirectional"))
      (node (ref "J16") (pin "30") (pinfunction "30_30") (pintype "bidirectional"))
      (node (ref "J17") (pin "30") (pinfunction "30_30") (pintype "bidirectional"))
      (node (ref "J5") (pin "30") (pinfunction "30_30") (pintype "bidirectional"))
      (node (ref "J6") (pin "30") (pinfunction "30_30") (pintype "bidirectional"))
      (node (ref "J7") (pin "30") (pinfunction "30_30") (pintype "bidirectional"))
      (node (ref "J9") (pin "30") (pinfunction "30_30") (pintype "bidirectional"))
    )
    (net (code "232") (name "P12V0_EEM") (class "Default")
      (node (ref "J10") (pin "28") (pinfunction "28_28") (pintype "bidirectional"))
      (node (ref "J10") (pin "29") (pinfunction "29_29") (pintype "bidirectional"))
      (node (ref "J11") (pin "28") (pinfunction "28_28") (pintype "bidirectional"))
      (node (ref "J11") (pin "29") (pinfunction "29_29") (pintype "bidirectional"))
      (node (ref "J12") (pin "28") (pinfunction "28_28") (pintype "bidirectional"))
      (node (ref "J12") (pin "29") (pinfunction "29_29") (pintype "bidirectional"))
      (node (ref "J13") (pin "28") (pinfunction "28_28") (pintype "bidirectional"))
      (node (ref "J13") (pin "29") (pinfunction "29_29") (pintype "bidirectional"))
      (node (ref "J14") (pin "28") (pinfunction "28_28") (pintype "bidirectional"))
      (node (ref "J14") (pin "29") (pinfunction "29_29") (pintype "bidirectional"))
      (node (ref "J15") (pin "28") (pinfunction "28_28") (pintype "bidirectional"))
      (node (ref "J15") (pin "29") (pinfunction "29_29") (pintype "bidirectional"))
      (node (ref "J16") (pin "28") (pinfunction "28_28") (pintype "bidirectional"))
      (node (ref "J16") (pin "29") (pinfunction "29_29") (pintype "bidirectional"))
      (node (ref "J17") (pin "28") (pinfunction "28_28") (pintype "bidirectional"))
      (node (ref "J17") (pin "29") (pinfunction "29_29") (pintype "bidirectional"))
      (node (ref "J5") (pin "28") (pinfunction "28_28") (pintype "bidirectional"))
      (node (ref "J5") (pin "29") (pinfunction "29_29") (pintype "bidirectional"))
      (node (ref "J6") (pin "28") (pinfunction "28_28") (pintype "bidirectional"))
      (node (ref "J6") (pin "29") (pinfunction "29_29") (pintype "bidirectional"))
      (node (ref "J7") (pin "28") (pinfunction "28_28") (pintype "bidirectional"))
      (node (ref "J7") (pin "29") (pinfunction "29_29") (pintype "bidirectional"))
      (node (ref "J9") (pin "28") (pinfunction "28_28") (pintype "bidirectional"))
      (node (ref "J9") (pin "29") (pinfunction "29_29") (pintype "bidirectional"))
    )
  )
)
